# pmod_clock_83c0b260.net
KiCad netlist of a schematic drawn in EAGLE
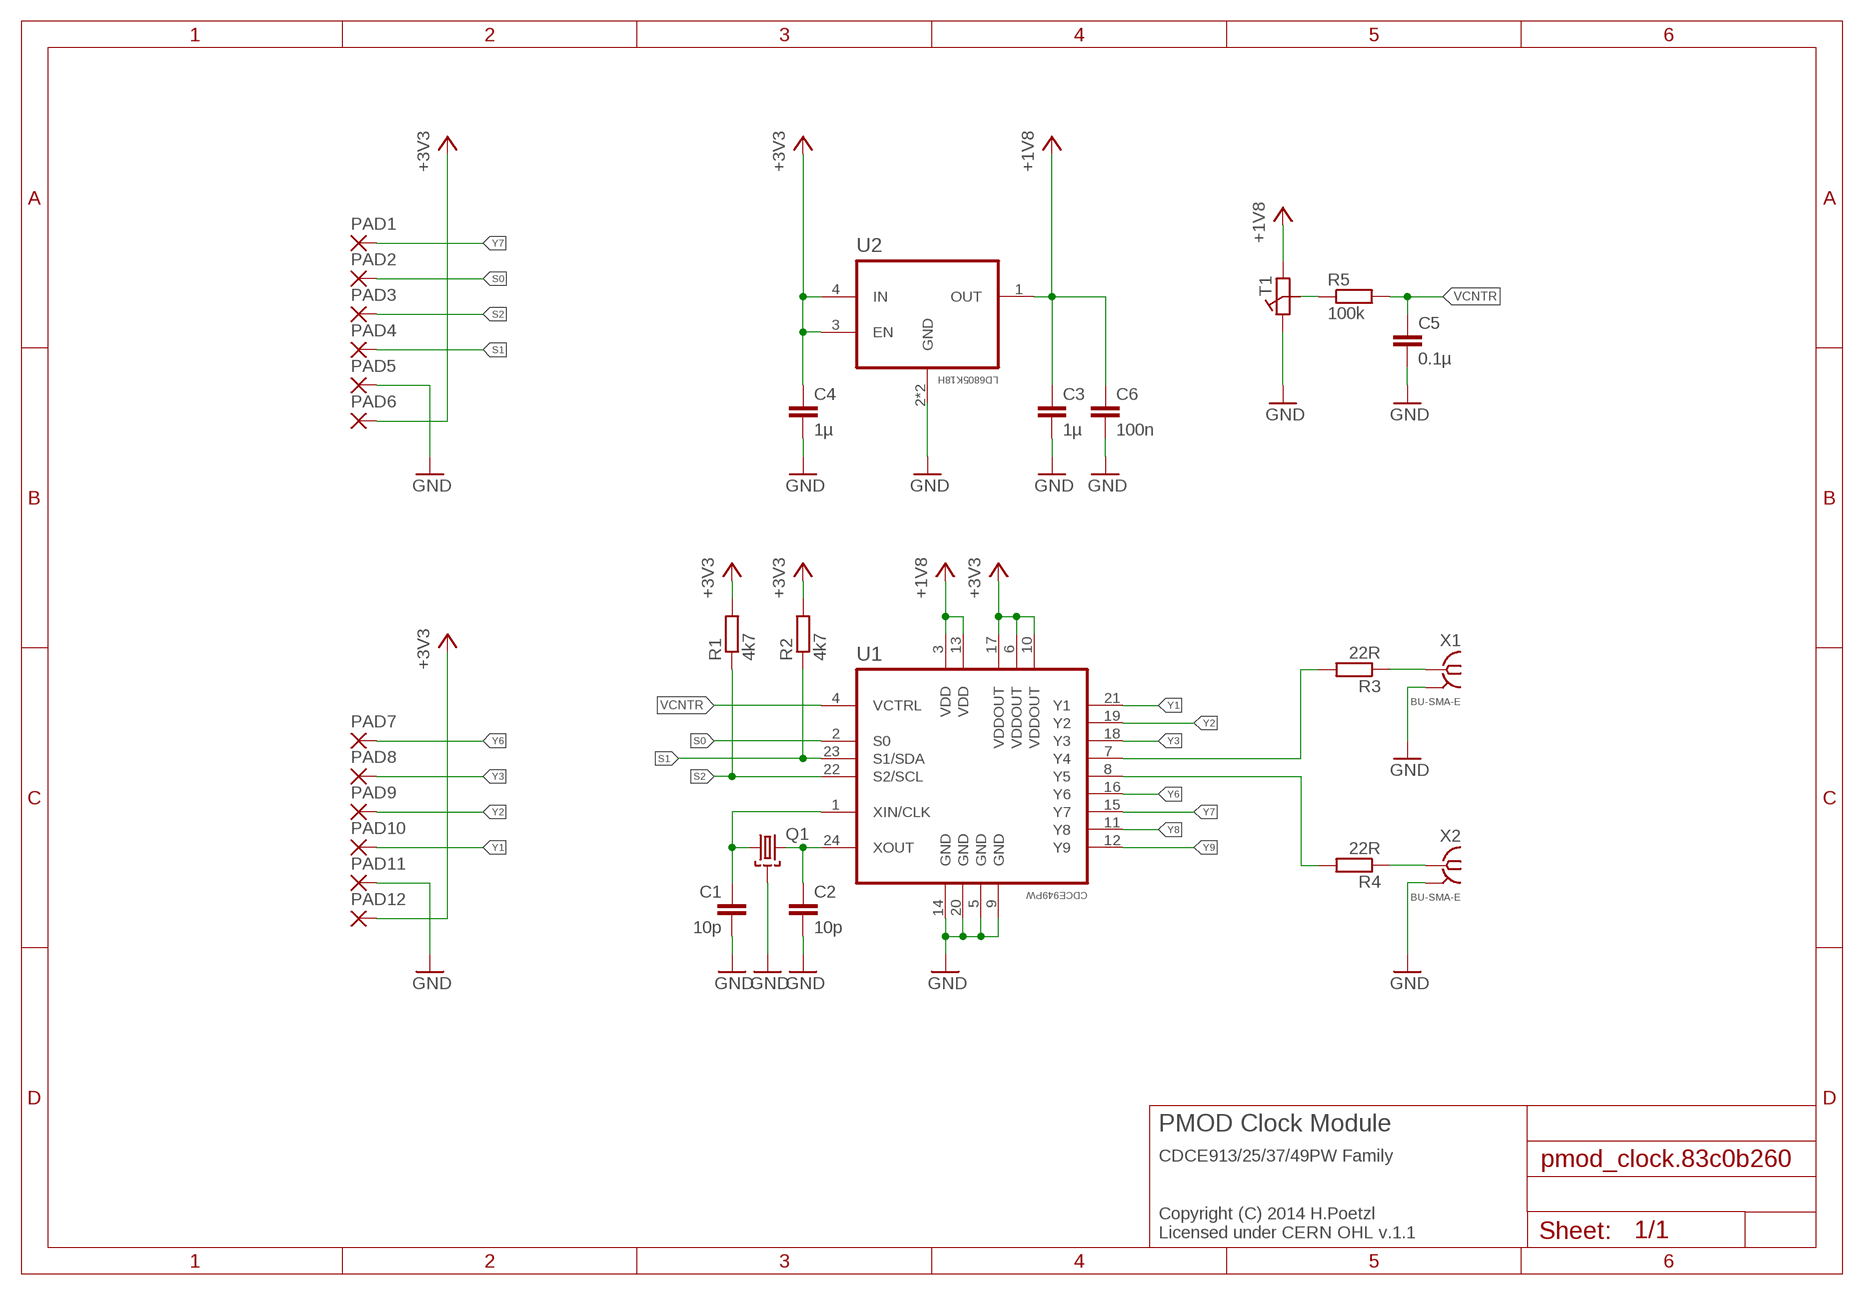
[diagram p0: schematic, sheet 1]

(export (version "E")
  (design (tool "Eeschema 10.0.6"))
  (components
    (comp (ref "C1")
      (value "10p")
      (footprint "eagle-import:C0402K")
      (libsource (lib "eagle-import") (part "C-EUC0402K"))
    )
    (comp (ref "C2")
      (value "10p")
      (footprint "eagle-import:C0402K")
      (libsource (lib "eagle-import") (part "C-EUC0402K"))
    )
    (comp (ref "C3")
      (value "1µ")
      (footprint "eagle-import:C0402")
      (libsource (lib "eagle-import") (part "C-EUC0402"))
    )
    (comp (ref "C4")
      (value "1µ")
      (footprint "eagle-import:C0402")
      (libsource (lib "eagle-import") (part "C-EUC0402"))
    )
    (comp (ref "C5")
      (value "0.1µ")
      (footprint "eagle-import:C0402")
      (libsource (lib "eagle-import") (part "C-EUC0402"))
    )
    (comp (ref "C6")
      (value "100n")
      (footprint "eagle-import:C0402")
      (libsource (lib "eagle-import") (part "C-EUC0402"))
    )
    (comp (ref "PAD1")
      (value "SMD2HR")
      (footprint "eagle-import:SMD1.27-3.175HR")
      (libsource (lib "eagle-import") (part "SMD2HR"))
    )
    (comp (ref "PAD2")
      (value "SMD2HR")
      (footprint "eagle-import:SMD1.27-3.175HR")
      (libsource (lib "eagle-import") (part "SMD2HR"))
    )
    (comp (ref "PAD3")
      (value "SMD2HR")
      (footprint "eagle-import:SMD1.27-3.175HR")
      (libsource (lib "eagle-import") (part "SMD2HR"))
    )
    (comp (ref "PAD4")
      (value "SMD2HR")
      (footprint "eagle-import:SMD1.27-3.175HR")
      (libsource (lib "eagle-import") (part "SMD2HR"))
    )
    (comp (ref "PAD5")
      (value "SMD2HR")
      (footprint "eagle-import:SMD1.27-3.175HR")
      (libsource (lib "eagle-import") (part "SMD2HR"))
    )
    (comp (ref "PAD6")
      (value "SMD2HR")
      (footprint "eagle-import:SMD1.27-3.175HR")
      (libsource (lib "eagle-import") (part "SMD2HR"))
    )
    (comp (ref "PAD7")
      (value "SMD2HR")
      (footprint "eagle-import:SMD1.27-3.175HR")
      (libsource (lib "eagle-import") (part "SMD2HR"))
    )
    (comp (ref "PAD8")
      (value "SMD2HR")
      (footprint "eagle-import:SMD1.27-3.175HR")
      (libsource (lib "eagle-import") (part "SMD2HR"))
    )
    (comp (ref "PAD9")
      (value "SMD2HR")
      (footprint "eagle-import:SMD1.27-3.175HR")
      (libsource (lib "eagle-import") (part "SMD2HR"))
    )
    (comp (ref "PAD10")
      (value "SMD2HR")
      (footprint "eagle-import:SMD1.27-3.175HR")
      (libsource (lib "eagle-import") (part "SMD2HR"))
    )
    (comp (ref "PAD11")
      (value "SMD2HR")
      (footprint "eagle-import:SMD1.27-3.175HR")
      (libsource (lib "eagle-import") (part "SMD2HR"))
    )
    (comp (ref "PAD12")
      (value "SMD2HR")
      (footprint "eagle-import:SMD1.27-3.175HR")
      (libsource (lib "eagle-import") (part "SMD2HR"))
    )
    (comp (ref "Q1")
      (value "SMD-4P-2G5.0X3.2+3.2X2.5")
      (footprint "eagle-import:MIX")
      (libsource (lib "eagle-import") (part "SMD-4P-2G5.0X3.2+3.2X2.5"))
    )
    (comp (ref "R1")
      (value "4k7")
      (footprint "eagle-import:R0402")
      (libsource (lib "eagle-import") (part "R-EU_R0402"))
    )
    (comp (ref "R2")
      (value "4k7")
      (footprint "eagle-import:R0402")
      (libsource (lib "eagle-import") (part "R-EU_R0402"))
    )
    (comp (ref "R3")
      (value "22R")
      (footprint "eagle-import:R0402")
      (libsource (lib "eagle-import") (part "R-EU_R0402"))
    )
    (comp (ref "R4")
      (value "22R")
      (footprint "eagle-import:R0402")
      (libsource (lib "eagle-import") (part "R-EU_R0402"))
    )
    (comp (ref "R5")
      (value "100k")
      (footprint "eagle-import:R0402")
      (libsource (lib "eagle-import") (part "R-EU_R0402"))
    )
    (comp (ref "T1")
      (value "PVZ2A")
      (footprint "eagle-import:TRIM-PVZ2A")
      (libsource (lib "eagle-import") (part "PVZ2A"))
    )
    (comp (ref "U1")
      (value "CDCE949PW")
      (footprint "eagle-import:SOP65P640X120-24N")
      (libsource (lib "eagle-import") (part "CDCE949PW"))
    )
    (comp (ref "U2")
      (value "LD6805K18H")
      (footprint "eagle-import:NXP_LD6805")
      (fields (field (name "MPN") "LD6805K/18H"))
      (libsource (lib "eagle-import") (part "LD6805K18H"))
    )
    (comp (ref "X1")
      (value "BU-SMA-E")
      (footprint "eagle-import:SMA-EDGE")
      (libsource (lib "eagle-import") (part "BU-SMA-E"))
    )
    (comp (ref "X2")
      (value "BU-SMA-E")
      (footprint "eagle-import:SMA-EDGE")
      (libsource (lib "eagle-import") (part "BU-SMA-E"))
    )
  )
  (nets
    (net (code "1") (name "+1V8") (class "Default")
      (node (ref "C3") (pin "1") (pinfunction "1_1") (pintype "passive"))
      (node (ref "C6") (pin "1") (pinfunction "1_1") (pintype "passive"))
      (node (ref "T1") (pin "1") (pinfunction "A_1") (pintype "bidirectional"))
      (node (ref "U1") (pin "13") (pinfunction "VDD_13") (pintype "power_in"))
      (node (ref "U1") (pin "3") (pinfunction "VDD_3") (pintype "power_in"))
      (node (ref "U2") (pin "1") (pinfunction "OUT_1") (pintype "power_in"))
    )
    (net (code "2") (name "+3V3") (class "Default")
      (node (ref "C4") (pin "1") (pinfunction "1_1") (pintype "passive"))
      (node (ref "PAD12") (pin "1") (pinfunction "P_1") (pintype "passive"))
      (node (ref "PAD6") (pin "1") (pinfunction "P_1") (pintype "passive"))
      (node (ref "R1") (pin "2") (pinfunction "2_2") (pintype "passive"))
      (node (ref "R2") (pin "2") (pinfunction "2_2") (pintype "passive"))
      (node (ref "U1") (pin "10") (pinfunction "VDDOUT_10") (pintype "power_in"))
      (node (ref "U1") (pin "17") (pinfunction "VDDOUT_17") (pintype "power_in"))
      (node (ref "U1") (pin "6") (pinfunction "VDDOUT_6") (pintype "power_in"))
      (node (ref "U2") (pin "3") (pinfunction "EN_3") (pintype "input"))
      (node (ref "U2") (pin "4") (pinfunction "IN_4") (pintype "power_in"))
    )
    (net (code "3") (name "GND") (class "Default")
      (node (ref "C1") (pin "2") (pinfunction "2_2") (pintype "passive"))
      (node (ref "C2") (pin "2") (pinfunction "2_2") (pintype "passive"))
      (node (ref "C3") (pin "2") (pinfunction "2_2") (pintype "passive"))
      (node (ref "C4") (pin "2") (pinfunction "2_2") (pintype "passive"))
      (node (ref "C5") (pin "2") (pinfunction "2_2") (pintype "passive"))
      (node (ref "C6") (pin "2") (pinfunction "2_2") (pintype "passive"))
      (node (ref "PAD11") (pin "1") (pinfunction "P_1") (pintype "passive"))
      (node (ref "PAD5") (pin "1") (pinfunction "P_1") (pintype "passive"))
      (node (ref "Q1") (pin "2") (pinfunction "GND_2") (pintype "power_in"))
      (node (ref "Q1") (pin "2@") (pinfunction "GND_2@") (pintype "power_in"))
      (node (ref "Q1") (pin "4") (pinfunction "GND_4") (pintype "power_in"))
      (node (ref "Q1") (pin "4@") (pinfunction "GND_4@") (pintype "power_in"))
      (node (ref "T1") (pin "3") (pinfunction "C_3") (pintype "bidirectional"))
      (node (ref "U1") (pin "14") (pinfunction "GND_14") (pintype "passive"))
      (node (ref "U1") (pin "20") (pinfunction "GND_20") (pintype "passive"))
      (node (ref "U1") (pin "5") (pinfunction "GND_5") (pintype "passive"))
      (node (ref "U1") (pin "9") (pinfunction "GND_9") (pintype "passive"))
      (node (ref "U2") (pin "2") (pinfunction "GND_2") (pintype "power_in"))
      (node (ref "U2") (pin "5") (pinfunction "GND_5") (pintype "power_in"))
      (node (ref "X1") (pin "2@3") (pinfunction "2_2@3") (pintype "passive"))
      (node (ref "X1") (pin "2@4") (pinfunction "2_2@4") (pintype "passive"))
      (node (ref "X2") (pin "2@3") (pinfunction "2_2@3") (pintype "passive"))
      (node (ref "X2") (pin "2@4") (pinfunction "2_2@4") (pintype "passive"))
    )
    (net (code "4") (name "Net-(R3-Pad1)") (class "Default")
      (node (ref "R3") (pin "1") (pinfunction "1_1") (pintype "passive"))
      (node (ref "X1") (pin "1") (pinfunction "1_1") (pintype "passive"))
    )
    (net (code "5") (name "Net-(R4-Pad1)") (class "Default")
      (node (ref "R4") (pin "1") (pinfunction "1_1") (pintype "passive"))
      (node (ref "X2") (pin "1") (pinfunction "1_1") (pintype "passive"))
    )
    (net (code "6") (name "Net-(T1-B)") (class "Default")
      (node (ref "R5") (pin "1") (pinfunction "1_1") (pintype "passive"))
      (node (ref "T1") (pin "2") (pinfunction "B_2") (pintype "bidirectional"))
    )
    (net (code "7") (name "Net-(U1-XIN{slash}CLK)") (class "Default")
      (node (ref "C1") (pin "1") (pinfunction "1_1") (pintype "passive"))
      (node (ref "Q1") (pin "1") (pinfunction "1_1") (pintype "passive"))
      (node (ref "Q1") (pin "1@") (pinfunction "1_1@") (pintype "passive"))
      (node (ref "U1") (pin "1") (pinfunction "XIN/CLK_1") (pintype "input"))
    )
    (net (code "8") (name "Net-(U1-XOUT)") (class "Default")
      (node (ref "C2") (pin "1") (pinfunction "1_1") (pintype "passive"))
      (node (ref "Q1") (pin "3") (pinfunction "2_3") (pintype "passive"))
      (node (ref "Q1") (pin "3@") (pinfunction "2_3@") (pintype "passive"))
      (node (ref "U1") (pin "24") (pinfunction "XOUT_24") (pintype "output"))
    )
    (net (code "9") (name "Net-(U1-Y4)") (class "Default")
      (node (ref "R3") (pin "2") (pinfunction "2_2") (pintype "passive"))
      (node (ref "U1") (pin "7") (pinfunction "Y4_7") (pintype "output"))
    )
    (net (code "10") (name "Net-(U1-Y5)") (class "Default")
      (node (ref "R4") (pin "2") (pinfunction "2_2") (pintype "passive"))
      (node (ref "U1") (pin "8") (pinfunction "Y5_8") (pintype "output"))
    )
    (net (code "11") (name "S0") (class "Default")
      (node (ref "PAD2") (pin "1") (pinfunction "P_1") (pintype "passive"))
      (node (ref "U1") (pin "2") (pinfunction "S0_2") (pintype "input"))
    )
    (net (code "12") (name "S1") (class "Default")
      (node (ref "PAD4") (pin "1") (pinfunction "P_1") (pintype "passive"))
      (node (ref "R2") (pin "1") (pinfunction "1_1") (pintype "passive"))
      (node (ref "U1") (pin "23") (pinfunction "S1/SDA_23") (pintype "bidirectional"))
    )
    (net (code "13") (name "S2") (class "Default")
      (node (ref "PAD3") (pin "1") (pinfunction "P_1") (pintype "passive"))
      (node (ref "R1") (pin "1") (pinfunction "1_1") (pintype "passive"))
      (node (ref "U1") (pin "22") (pinfunction "S2/SCL_22") (pintype "input"))
    )
    (net (code "14") (name "VCNTR") (class "Default")
      (node (ref "C5") (pin "1") (pinfunction "1_1") (pintype "passive"))
      (node (ref "R5") (pin "2") (pinfunction "2_2") (pintype "passive"))
      (node (ref "U1") (pin "4") (pinfunction "VCTRL_4") (pintype "input"))
    )
    (net (code "15") (name "Y1") (class "Default")
      (node (ref "PAD10") (pin "1") (pinfunction "P_1") (pintype "passive"))
      (node (ref "U1") (pin "21") (pinfunction "Y1_21") (pintype "output"))
    )
    (net (code "16") (name "Y2") (class "Default")
      (node (ref "PAD9") (pin "1") (pinfunction "P_1") (pintype "passive"))
      (node (ref "U1") (pin "19") (pinfunction "Y2_19") (pintype "output"))
    )
    (net (code "17") (name "Y3") (class "Default")
      (node (ref "PAD8") (pin "1") (pinfunction "P_1") (pintype "passive"))
      (node (ref "U1") (pin "18") (pinfunction "Y3_18") (pintype "output"))
    )
    (net (code "18") (name "Y6") (class "Default")
      (node (ref "PAD7") (pin "1") (pinfunction "P_1") (pintype "passive"))
      (node (ref "U1") (pin "16") (pinfunction "Y6_16") (pintype "output"))
    )
    (net (code "19") (name "Y7") (class "Default")
      (node (ref "PAD1") (pin "1") (pinfunction "P_1") (pintype "passive"))
      (node (ref "U1") (pin "15") (pinfunction "Y7_15") (pintype "output"))
    )
    (net (code "20") (name "Y8") (class "Default")
      (node (ref "U1") (pin "11") (pinfunction "Y8_11") (pintype "output"))
    )
    (net (code "21") (name "Y9") (class "Default")
      (node (ref "U1") (pin "12") (pinfunction "Y9_12") (pintype "output"))
    )
  )
)
